# A214B.net
KiCad netlist of a schematic drawn in EAGLE
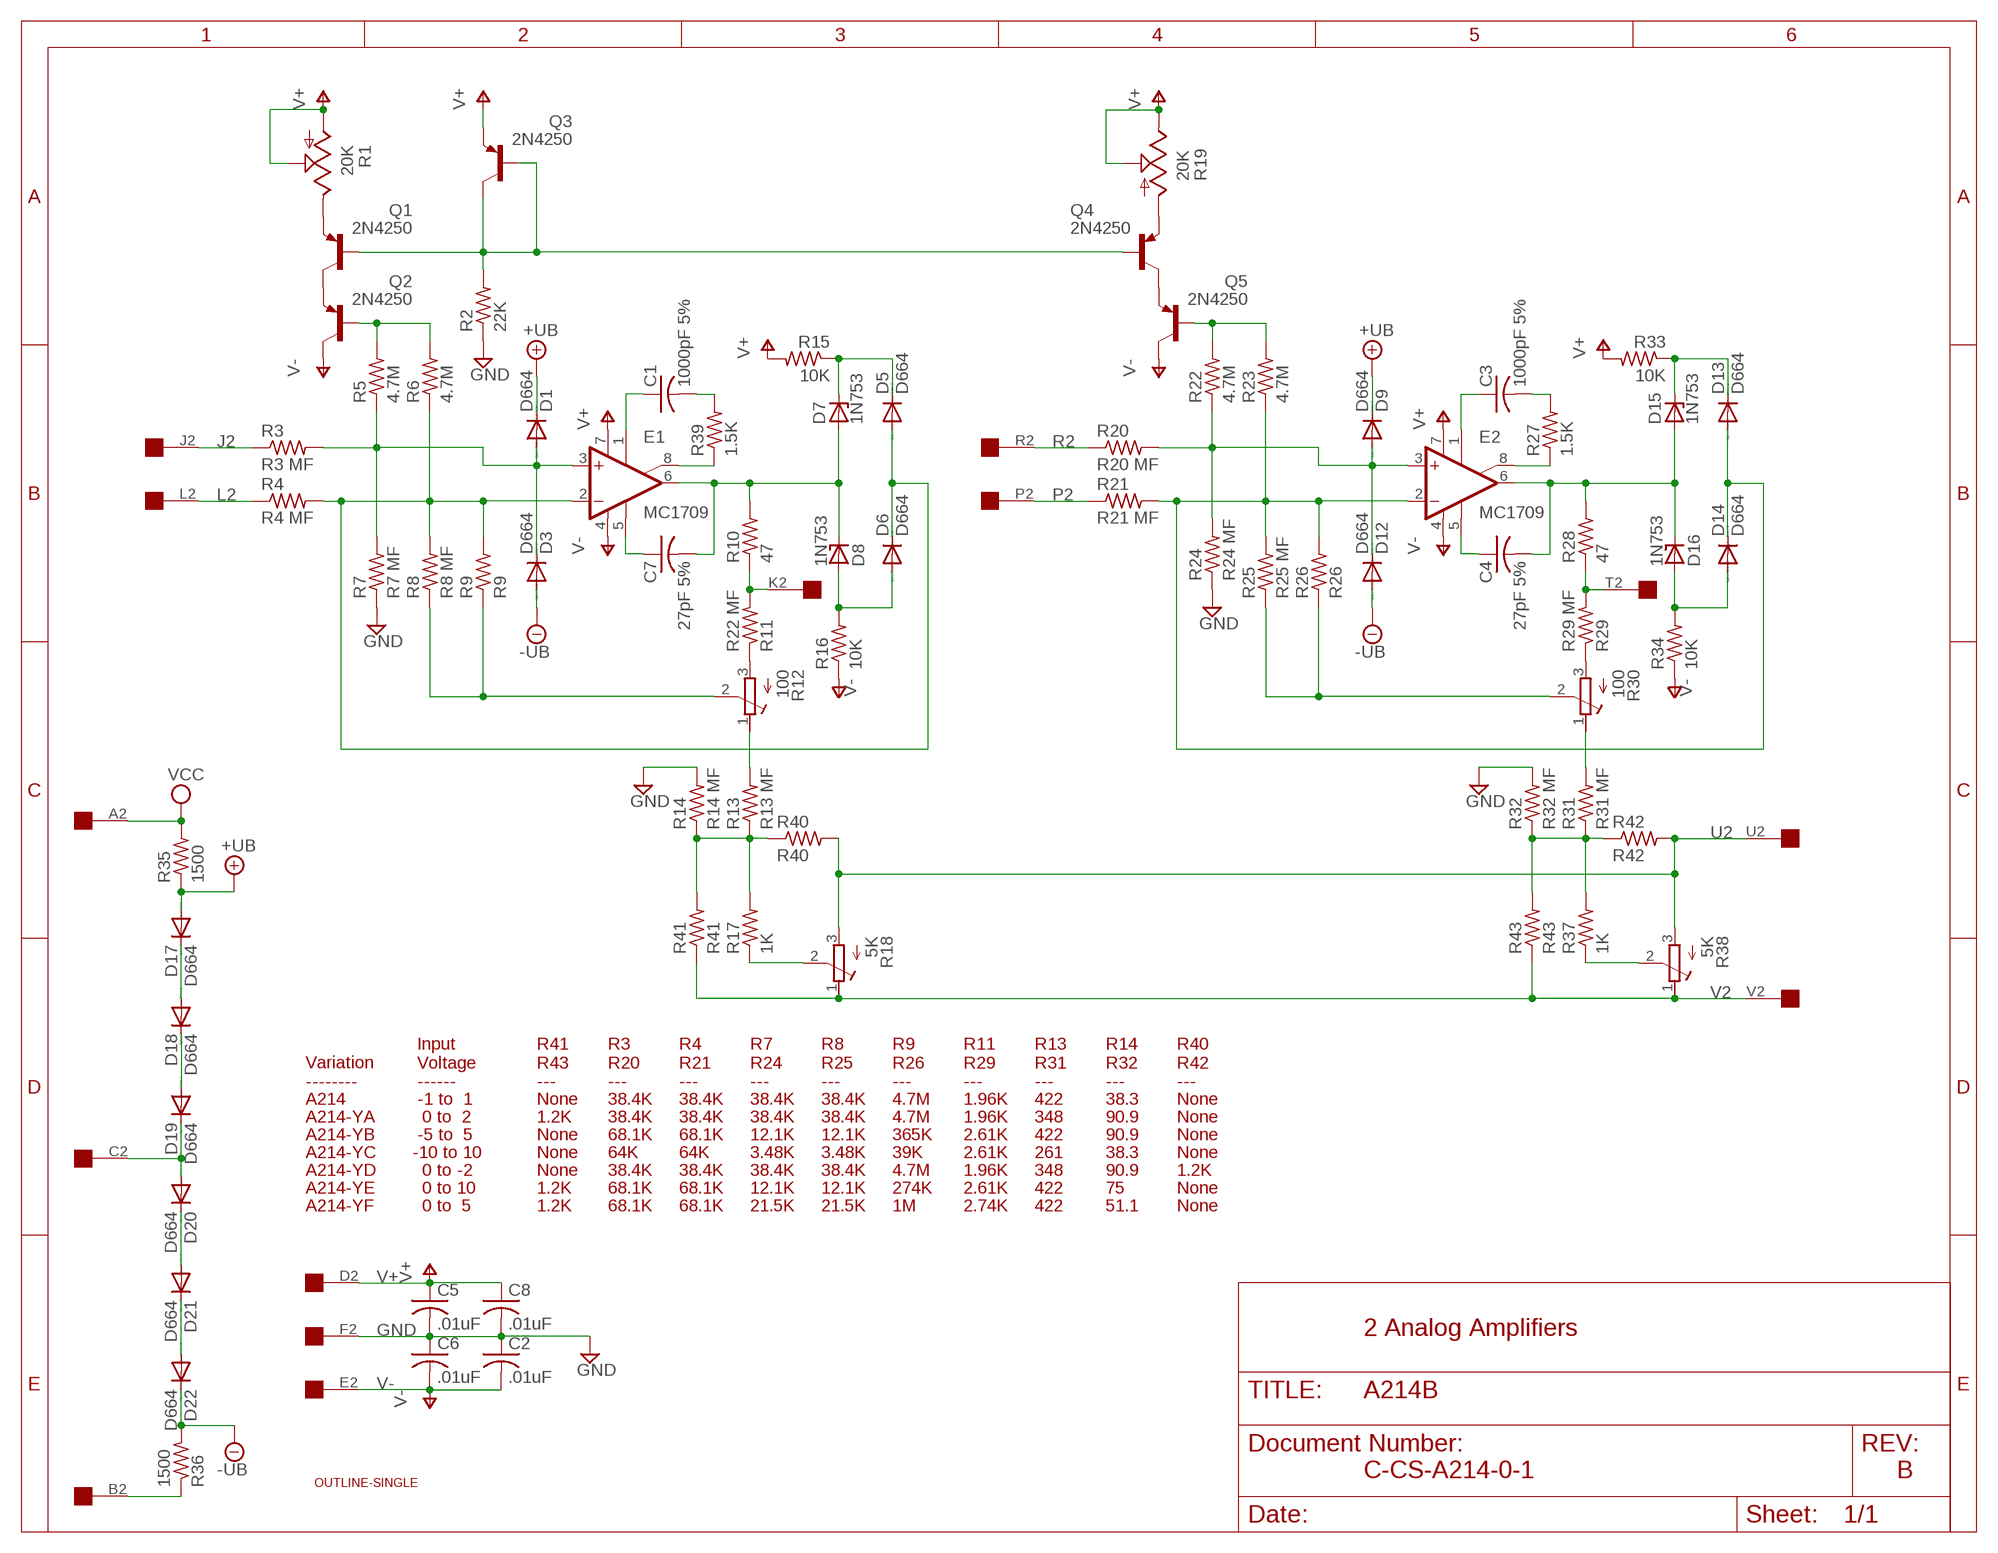
[diagram p0: schematic, sheet 1]

(export (version "E")
  (design (tool "Eeschema 10.0.6"))
  (components
    (comp (ref "C1")
      (value "1000pF 5%")
      (footprint "eagle-import:C050-030X075")
      (libsource (lib "eagle-import") (part "C-US050-030X075"))
    )
    (comp (ref "C2")
      (value ".01uF")
      (footprint "eagle-import:C063-025X075")
      (libsource (lib "eagle-import") (part "C-US"))
    )
    (comp (ref "C3")
      (value "1000pF 5%")
      (footprint "eagle-import:C050-030X075")
      (libsource (lib "eagle-import") (part "C-US050-030X075"))
    )
    (comp (ref "C4")
      (value "27pF 5%")
      (footprint "eagle-import:C063-025X075")
      (libsource (lib "eagle-import") (part "C-US"))
    )
    (comp (ref "C5")
      (value ".01uF")
      (footprint "eagle-import:C063-025X075")
      (libsource (lib "eagle-import") (part "C-US"))
    )
    (comp (ref "C6")
      (value ".01uF")
      (footprint "eagle-import:C063-025X075")
      (libsource (lib "eagle-import") (part "C-US"))
    )
    (comp (ref "C7")
      (value "27pF 5%")
      (footprint "eagle-import:C063-025X075")
      (libsource (lib "eagle-import") (part "C-US"))
    )
    (comp (ref "C8")
      (value ".01uF")
      (footprint "eagle-import:C063-025X075")
      (libsource (lib "eagle-import") (part "C-US"))
    )
    (comp (ref "D1")
      (value "D664")
      (footprint "eagle-import:DO35-10")
      (libsource (lib "eagle-import") (part "DIODE-DO35-10"))
    )
    (comp (ref "D3")
      (value "D664")
      (footprint "eagle-import:DO35-10")
      (libsource (lib "eagle-import") (part "DIODE-DO35-10"))
    )
    (comp (ref "D5")
      (value "D664")
      (footprint "eagle-import:DO35-10")
      (libsource (lib "eagle-import") (part "DIODE-DO35-10"))
    )
    (comp (ref "D6")
      (value "D664")
      (footprint "eagle-import:DO35-10")
      (libsource (lib "eagle-import") (part "DIODE-DO35-10"))
    )
    (comp (ref "D7")
      (value "1N753")
      (footprint "eagle-import:DO41Z10")
      (libsource (lib "eagle-import") (part "ZENER-DIODEDO41Z10"))
    )
    (comp (ref "D8")
      (value "1N753")
      (footprint "eagle-import:DO41Z10")
      (libsource (lib "eagle-import") (part "ZENER-DIODEDO41Z10"))
    )
    (comp (ref "D9")
      (value "D664")
      (footprint "eagle-import:DO35-10")
      (libsource (lib "eagle-import") (part "DIODE-DO35-10"))
    )
    (comp (ref "D12")
      (value "D664")
      (footprint "eagle-import:DO35-10")
      (libsource (lib "eagle-import") (part "DIODE-DO35-10"))
    )
    (comp (ref "D13")
      (value "D664")
      (footprint "eagle-import:DO35-10")
      (libsource (lib "eagle-import") (part "DIODE-DO35-10"))
    )
    (comp (ref "D14")
      (value "D664")
      (footprint "eagle-import:DO35-10")
      (libsource (lib "eagle-import") (part "DIODE-DO35-10"))
    )
    (comp (ref "D15")
      (value "1N753")
      (footprint "eagle-import:DO41Z10")
      (libsource (lib "eagle-import") (part "ZENER-DIODEDO41Z10"))
    )
    (comp (ref "D16")
      (value "1N753")
      (footprint "eagle-import:DO41Z10")
      (libsource (lib "eagle-import") (part "ZENER-DIODEDO41Z10"))
    )
    (comp (ref "D17")
      (value "D664")
      (footprint "eagle-import:DO35-10")
      (libsource (lib "eagle-import") (part "DIODE-DO35-10"))
    )
    (comp (ref "D18")
      (value "D664")
      (footprint "eagle-import:DO35-10")
      (libsource (lib "eagle-import") (part "DIODE-DO35-10"))
    )
    (comp (ref "D19")
      (value "D664")
      (footprint "eagle-import:DO35-10")
      (libsource (lib "eagle-import") (part "DIODE-DO35-10"))
    )
    (comp (ref "D20")
      (value "D664")
      (footprint "eagle-import:DO35-10")
      (libsource (lib "eagle-import") (part "DIODE-DO35-10"))
    )
    (comp (ref "D21")
      (value "D664")
      (footprint "eagle-import:DO35-10")
      (libsource (lib "eagle-import") (part "DIODE-DO35-10"))
    )
    (comp (ref "D22")
      (value "D664")
      (footprint "eagle-import:DO35-10")
      (libsource (lib "eagle-import") (part "DIODE-DO35-10"))
    )
    (comp (ref "E1")
      (value "MC1709")
      (footprint "eagle-import:H08C")
      (libsource (lib "eagle-import") (part "MC1709"))
    )
    (comp (ref "E2")
      (value "MC1709")
      (footprint "eagle-import:H08C")
      (libsource (lib "eagle-import") (part "MC1709"))
    )
    (comp (ref "Q1")
      (value "2N4250")
      (footprint "eagle-import:TO5")
      (libsource (lib "eagle-import") (part "-PNP-TO5"))
    )
    (comp (ref "Q2")
      (value "2N4250")
      (footprint "eagle-import:TO5")
      (libsource (lib "eagle-import") (part "-PNP-TO5"))
    )
    (comp (ref "Q3")
      (value "2N4250")
      (footprint "eagle-import:TO5")
      (libsource (lib "eagle-import") (part "-PNP-TO5"))
    )
    (comp (ref "Q4")
      (value "2N4250")
      (footprint "eagle-import:TO5")
      (libsource (lib "eagle-import") (part "-PNP-TO5"))
    )
    (comp (ref "Q5")
      (value "2N4250")
      (footprint "eagle-import:TO5")
      (libsource (lib "eagle-import") (part "-PNP-TO5"))
    )
    (comp (ref "R1")
      (value "20K")
      (footprint "eagle-import:B25P")
      (libsource (lib "eagle-import") (part "TRIM_US-B25P"))
    )
    (comp (ref "R2")
      (value "22K")
      (footprint "eagle-import:0207_10")
      (libsource (lib "eagle-import") (part "R-US_0207/10"))
    )
    (comp (ref "R3")
      (value "R3 MF")
      (footprint "eagle-import:0207_15")
      (libsource (lib "eagle-import") (part "R-US_0207/15"))
    )
    (comp (ref "R4")
      (value "R4 MF")
      (footprint "eagle-import:0207_15")
      (libsource (lib "eagle-import") (part "R-US_0207/15"))
    )
    (comp (ref "R5")
      (value "4.7M")
      (footprint "eagle-import:0207_10")
      (libsource (lib "eagle-import") (part "R-US_0207/10"))
    )
    (comp (ref "R6")
      (value "4.7M")
      (footprint "eagle-import:0207_10")
      (libsource (lib "eagle-import") (part "R-US_0207/10"))
    )
    (comp (ref "R7")
      (value "R7 MF")
      (footprint "eagle-import:0207_15")
      (libsource (lib "eagle-import") (part "R-US_0207/15"))
    )
    (comp (ref "R8")
      (value "R8 MF")
      (footprint "eagle-import:0207_15")
      (libsource (lib "eagle-import") (part "R-US_0207/15"))
    )
    (comp (ref "R9")
      (value "R9")
      (footprint "eagle-import:0207_10")
      (libsource (lib "eagle-import") (part "R-US_0207/10"))
    )
    (comp (ref "R10")
      (value "47")
      (footprint "eagle-import:0207_10")
      (libsource (lib "eagle-import") (part "R-US_0207/10"))
    )
    (comp (ref "R11")
      (value "R22 MF")
      (footprint "eagle-import:0207_15")
      (libsource (lib "eagle-import") (part "R-US_0207/15"))
    )
    (comp (ref "R12")
      (value "100")
      (footprint "eagle-import:3006Y")
      (libsource (lib "eagle-import") (part "275P"))
    )
    (comp (ref "R13")
      (value "R13 MF")
      (footprint "eagle-import:0207_15")
      (libsource (lib "eagle-import") (part "R-US_0207/15"))
    )
    (comp (ref "R14")
      (value "R14 MF")
      (footprint "eagle-import:0207_15")
      (libsource (lib "eagle-import") (part "R-US_0207/15"))
    )
    (comp (ref "R15")
      (value "10K")
      (footprint "eagle-import:0207_10")
      (libsource (lib "eagle-import") (part "R-US_0207/10"))
    )
    (comp (ref "R16")
      (value "10K")
      (footprint "eagle-import:0207_10")
      (libsource (lib "eagle-import") (part "R-US_0207/10"))
    )
    (comp (ref "R17")
      (value "1K")
      (footprint "eagle-import:0207_10")
      (libsource (lib "eagle-import") (part "R-US_0207/10"))
    )
    (comp (ref "R18")
      (value "5K")
      (footprint "eagle-import:3006Y")
      (libsource (lib "eagle-import") (part "275P"))
    )
    (comp (ref "R19")
      (value "20K")
      (footprint "eagle-import:B25P")
      (libsource (lib "eagle-import") (part "TRIM_US-B25P"))
    )
    (comp (ref "R20")
      (value "R20 MF")
      (footprint "eagle-import:0207_15")
      (libsource (lib "eagle-import") (part "R-US_0207/15"))
    )
    (comp (ref "R21")
      (value "R21 MF")
      (footprint "eagle-import:0207_15")
      (libsource (lib "eagle-import") (part "R-US_0207/15"))
    )
    (comp (ref "R22")
      (value "4.7M")
      (footprint "eagle-import:0207_10")
      (libsource (lib "eagle-import") (part "R-US_0207/10"))
    )
    (comp (ref "R23")
      (value "4.7M")
      (footprint "eagle-import:0207_10")
      (libsource (lib "eagle-import") (part "R-US_0207/10"))
    )
    (comp (ref "R24")
      (value "R24 MF")
      (footprint "eagle-import:0207_15")
      (libsource (lib "eagle-import") (part "R-US_0207/15"))
    )
    (comp (ref "R25")
      (value "R25 MF")
      (footprint "eagle-import:0207_15")
      (libsource (lib "eagle-import") (part "R-US_0207/15"))
    )
    (comp (ref "R26")
      (value "R26")
      (footprint "eagle-import:0207_10")
      (libsource (lib "eagle-import") (part "R-US_0207/10"))
    )
    (comp (ref "R27")
      (value "1.5K")
      (footprint "eagle-import:0207_10")
      (libsource (lib "eagle-import") (part "R-US_0207/10"))
    )
    (comp (ref "R28")
      (value "47")
      (footprint "eagle-import:0207_10")
      (libsource (lib "eagle-import") (part "R-US_0207/10"))
    )
    (comp (ref "R29")
      (value "R29 MF")
      (footprint "eagle-import:0207_15")
      (libsource (lib "eagle-import") (part "R-US_0207/15"))
    )
    (comp (ref "R30")
      (value "100")
      (footprint "eagle-import:3006Y")
      (libsource (lib "eagle-import") (part "275P"))
    )
    (comp (ref "R31")
      (value "R31 MF")
      (footprint "eagle-import:0207_15")
      (libsource (lib "eagle-import") (part "R-US_0207/15"))
    )
    (comp (ref "R32")
      (value "R32 MF")
      (footprint "eagle-import:0207_15")
      (libsource (lib "eagle-import") (part "R-US_0207/15"))
    )
    (comp (ref "R33")
      (value "10K")
      (footprint "eagle-import:0207_10")
      (libsource (lib "eagle-import") (part "R-US_0207/10"))
    )
    (comp (ref "R34")
      (value "10K")
      (footprint "eagle-import:0207_10")
      (libsource (lib "eagle-import") (part "R-US_0207/10"))
    )
    (comp (ref "R35")
      (value "1500")
      (footprint "eagle-import:0207_10")
      (libsource (lib "eagle-import") (part "R-US_0207/10"))
    )
    (comp (ref "R36")
      (value "1500")
      (footprint "eagle-import:0207_10")
      (libsource (lib "eagle-import") (part "R-US_0207/10"))
    )
    (comp (ref "R37")
      (value "1K")
      (footprint "eagle-import:0207_10")
      (libsource (lib "eagle-import") (part "R-US_0207/10"))
    )
    (comp (ref "R38")
      (value "5K")
      (footprint "eagle-import:3006Y")
      (libsource (lib "eagle-import") (part "275P"))
    )
    (comp (ref "R39")
      (value "1.5K")
      (footprint "eagle-import:0207_10")
      (libsource (lib "eagle-import") (part "R-US_0207/10"))
    )
    (comp (ref "R40")
      (value "R40")
      (footprint "eagle-import:0207_10")
      (libsource (lib "eagle-import") (part "R-US_0207/10"))
    )
    (comp (ref "R41")
      (value "R41")
      (footprint "eagle-import:0207_10")
      (libsource (lib "eagle-import") (part "R-US_0207/10"))
    )
    (comp (ref "R42")
      (value "R42")
      (footprint "eagle-import:0207_10")
      (libsource (lib "eagle-import") (part "R-US_0207/10"))
    )
    (comp (ref "R43")
      (value "R43")
      (footprint "eagle-import:0207_10")
      (libsource (lib "eagle-import") (part "R-US_0207/10"))
    )
    (comp (ref "U$1")
      (value "OUTLINE-SINGLE")
      (footprint "eagle-import:SINGLE")
      (libsource (lib "eagle-import") (part "OUTLINE-SINGLE"))
    )
    (comp (ref "U$2")
      (value "SINGLE")
      (footprint "eagle-import:EDGE-CON2")
      (libsource (lib "eagle-import") (part "SINGLE"))
    )
  )
  (nets
    (net (code "1") (name "+UB") (class "Default")
      (node (ref "D1") (pin "C") (pinfunction "C_C") (pintype "passive"))
      (node (ref "D17") (pin "A") (pinfunction "A_A") (pintype "passive"))
      (node (ref "D9") (pin "C") (pinfunction "C_C") (pintype "passive"))
      (node (ref "R35") (pin "1") (pinfunction "1_1") (pintype "passive"))
    )
    (net (code "2") (name "-UB") (class "Default")
      (node (ref "D12") (pin "A") (pinfunction "A_A") (pintype "passive"))
      (node (ref "D22") (pin "C") (pinfunction "C_C") (pintype "passive"))
      (node (ref "D3") (pin "A") (pinfunction "A_A") (pintype "passive"))
      (node (ref "R36") (pin "2") (pinfunction "2_2") (pintype "passive"))
    )
    (net (code "3") (name "/J2") (class "Default")
      (node (ref "R3") (pin "1") (pinfunction "1_1") (pintype "passive"))
      (node (ref "U$2") (pin "J2") (pinfunction "1_J2") (pintype "bidirectional"))
    )
    (net (code "4") (name "/L2") (class "Default")
      (node (ref "R4") (pin "1") (pinfunction "1_1") (pintype "passive"))
      (node (ref "U$2") (pin "L2") (pinfunction "1_L2") (pintype "bidirectional"))
    )
    (net (code "5") (name "/P2") (class "Default")
      (node (ref "R21") (pin "1") (pinfunction "1_1") (pintype "passive"))
      (node (ref "U$2") (pin "P2") (pinfunction "1_P2") (pintype "bidirectional"))
    )
    (net (code "6") (name "/R2") (class "Default")
      (node (ref "R20") (pin "1") (pinfunction "1_1") (pintype "passive"))
      (node (ref "U$2") (pin "R2") (pinfunction "1_R2") (pintype "bidirectional"))
    )
    (net (code "7") (name "/U2") (class "Default")
      (node (ref "R18") (pin "3") (pinfunction "E_3") (pintype "passive"))
      (node (ref "R38") (pin "3") (pinfunction "E_3") (pintype "passive"))
      (node (ref "R40") (pin "2") (pinfunction "2_2") (pintype "passive"))
      (node (ref "R42") (pin "2") (pinfunction "2_2") (pintype "passive"))
      (node (ref "U$2") (pin "U2") (pinfunction "1_U2") (pintype "bidirectional"))
    )
    (net (code "8") (name "/V2") (class "Default")
      (node (ref "R18") (pin "1") (pinfunction "A_1") (pintype "passive"))
      (node (ref "R38") (pin "1") (pinfunction "A_1") (pintype "passive"))
      (node (ref "R41") (pin "1") (pinfunction "1_1") (pintype "passive"))
      (node (ref "R43") (pin "1") (pinfunction "1_1") (pintype "passive"))
      (node (ref "U$2") (pin "V2") (pinfunction "1_V2") (pintype "bidirectional"))
    )
    (net (code "9") (name "GND") (class "Default")
      (node (ref "C2") (pin "1") (pinfunction "1_1") (pintype "passive"))
      (node (ref "C5") (pin "2") (pinfunction "2_2") (pintype "passive"))
      (node (ref "C6") (pin "1") (pinfunction "1_1") (pintype "passive"))
      (node (ref "C8") (pin "2") (pinfunction "2_2") (pintype "passive"))
      (node (ref "R14") (pin "2") (pinfunction "2_2") (pintype "passive"))
      (node (ref "R2") (pin "1") (pinfunction "1_1") (pintype "passive"))
      (node (ref "R24") (pin "1") (pinfunction "1_1") (pintype "passive"))
      (node (ref "R32") (pin "2") (pinfunction "2_2") (pintype "passive"))
      (node (ref "R7") (pin "1") (pinfunction "1_1") (pintype "passive"))
      (node (ref "U$2") (pin "F2") (pinfunction "1_F2") (pintype "bidirectional"))
    )
    (net (code "10") (name "Net-(C1-Pad2)") (class "Default")
      (node (ref "C1") (pin "2") (pinfunction "2_2") (pintype "passive"))
      (node (ref "R39") (pin "2") (pinfunction "2_2") (pintype "passive"))
    )
    (net (code "11") (name "Net-(C3-Pad2)") (class "Default")
      (node (ref "C3") (pin "2") (pinfunction "2_2") (pintype "passive"))
      (node (ref "R27") (pin "2") (pinfunction "2_2") (pintype "passive"))
    )
    (net (code "12") (name "Net-(D5-PadC)") (class "Default")
      (node (ref "D5") (pin "C") (pinfunction "C_C") (pintype "passive"))
      (node (ref "D7") (pin "C") (pinfunction "C_C") (pintype "passive"))
      (node (ref "R15") (pin "1") (pinfunction "1_1") (pintype "passive"))
    )
    (net (code "13") (name "Net-(D6-PadA)") (class "Default")
      (node (ref "D6") (pin "A") (pinfunction "A_A") (pintype "passive"))
      (node (ref "D8") (pin "A") (pinfunction "A_A") (pintype "passive"))
      (node (ref "R16") (pin "2") (pinfunction "2_2") (pintype "passive"))
    )
    (net (code "14") (name "Net-(D13-PadC)") (class "Default")
      (node (ref "D13") (pin "C") (pinfunction "C_C") (pintype "passive"))
      (node (ref "D15") (pin "C") (pinfunction "C_C") (pintype "passive"))
      (node (ref "R33") (pin "1") (pinfunction "1_1") (pintype "passive"))
    )
    (net (code "15") (name "Net-(D14-PadA)") (class "Default")
      (node (ref "D14") (pin "A") (pinfunction "A_A") (pintype "passive"))
      (node (ref "D16") (pin "A") (pinfunction "A_A") (pintype "passive"))
      (node (ref "R34") (pin "2") (pinfunction "2_2") (pintype "passive"))
    )
    (net (code "16") (name "Net-(D17-PadC)") (class "Default")
      (node (ref "D17") (pin "C") (pinfunction "C_C") (pintype "passive"))
      (node (ref "D18") (pin "A") (pinfunction "A_A") (pintype "passive"))
    )
    (net (code "17") (name "Net-(D18-PadC)") (class "Default")
      (node (ref "D18") (pin "C") (pinfunction "C_C") (pintype "passive"))
      (node (ref "D19") (pin "A") (pinfunction "A_A") (pintype "passive"))
    )
    (net (code "18") (name "Net-(D20-PadC)") (class "Default")
      (node (ref "D20") (pin "C") (pinfunction "C_C") (pintype "passive"))
      (node (ref "D21") (pin "A") (pinfunction "A_A") (pintype "passive"))
    )
    (net (code "19") (name "Net-(D21-PadC)") (class "Default")
      (node (ref "D21") (pin "C") (pinfunction "C_C") (pintype "passive"))
      (node (ref "D22") (pin "A") (pinfunction "A_A") (pintype "passive"))
    )
    (net (code "20") (name "Net-(E1-+IN)") (class "Default")
      (node (ref "D1") (pin "A") (pinfunction "A_A") (pintype "passive"))
      (node (ref "D3") (pin "C") (pinfunction "C_C") (pintype "passive"))
      (node (ref "E1") (pin "3") (pinfunction "+IN_3") (pintype "input"))
      (node (ref "R3") (pin "2") (pinfunction "2_2") (pintype "passive"))
      (node (ref "R5") (pin "1") (pinfunction "1_1") (pintype "passive"))
      (node (ref "R7") (pin "2") (pinfunction "2_2") (pintype "passive"))
    )
    (net (code "21") (name "Net-(E1--IN)") (class "Default")
      (node (ref "D5") (pin "A") (pinfunction "A_A") (pintype "passive"))
      (node (ref "D6") (pin "C") (pinfunction "C_C") (pintype "passive"))
      (node (ref "E1") (pin "2") (pinfunction "-IN_2") (pintype "input"))
      (node (ref "R4") (pin "2") (pinfunction "2_2") (pintype "passive"))
      (node (ref "R6") (pin "1") (pinfunction "1_1") (pintype "passive"))
      (node (ref "R8") (pin "2") (pinfunction "2_2") (pintype "passive"))
      (node (ref "R9") (pin "2") (pinfunction "2_2") (pintype "passive"))
    )
    (net (code "22") (name "Net-(E1-ON1)") (class "Default")
      (node (ref "C1") (pin "1") (pinfunction "1_1") (pintype "passive"))
      (node (ref "E1") (pin "1") (pinfunction "ON1_1") (pintype "passive"))
    )
    (net (code "23") (name "Net-(E1-ON2)") (class "Default")
      (node (ref "E1") (pin "8") (pinfunction "ON2_8") (pintype "passive"))
      (node (ref "R39") (pin "1") (pinfunction "1_1") (pintype "passive"))
    )
    (net (code "24") (name "Net-(E1-OPT)") (class "Default")
      (node (ref "C7") (pin "1") (pinfunction "1_1") (pintype "passive"))
      (node (ref "E1") (pin "5") (pinfunction "OPT_5") (pintype "passive"))
    )
    (net (code "25") (name "Net-(E1-OUT)") (class "Default")
      (node (ref "C7") (pin "2") (pinfunction "2_2") (pintype "passive"))
      (node (ref "D7") (pin "A") (pinfunction "A_A") (pintype "passive"))
      (node (ref "D8") (pin "C") (pinfunction "C_C") (pintype "passive"))
      (node (ref "E1") (pin "6") (pinfunction "OUT_6") (pintype "output"))
      (node (ref "R10") (pin "2") (pinfunction "2_2") (pintype "passive"))
    )
    (net (code "26") (name "Net-(E2-+IN)") (class "Default")
      (node (ref "D12") (pin "C") (pinfunction "C_C") (pintype "passive"))
      (node (ref "D9") (pin "A") (pinfunction "A_A") (pintype "passive"))
      (node (ref "E2") (pin "3") (pinfunction "+IN_3") (pintype "input"))
      (node (ref "R20") (pin "2") (pinfunction "2_2") (pintype "passive"))
      (node (ref "R22") (pin "1") (pinfunction "1_1") (pintype "passive"))
      (node (ref "R24") (pin "2") (pinfunction "2_2") (pintype "passive"))
    )
    (net (code "27") (name "Net-(E2--IN)") (class "Default")
      (node (ref "D13") (pin "A") (pinfunction "A_A") (pintype "passive"))
      (node (ref "D14") (pin "C") (pinfunction "C_C") (pintype "passive"))
      (node (ref "E2") (pin "2") (pinfunction "-IN_2") (pintype "input"))
      (node (ref "R21") (pin "2") (pinfunction "2_2") (pintype "passive"))
      (node (ref "R23") (pin "1") (pinfunction "1_1") (pintype "passive"))
      (node (ref "R25") (pin "2") (pinfunction "2_2") (pintype "passive"))
      (node (ref "R26") (pin "2") (pinfunction "2_2") (pintype "passive"))
    )
    (net (code "28") (name "Net-(E2-ON1)") (class "Default")
      (node (ref "C3") (pin "1") (pinfunction "1_1") (pintype "passive"))
      (node (ref "E2") (pin "1") (pinfunction "ON1_1") (pintype "passive"))
    )
    (net (code "29") (name "Net-(E2-ON2)") (class "Default")
      (node (ref "E2") (pin "8") (pinfunction "ON2_8") (pintype "passive"))
      (node (ref "R27") (pin "1") (pinfunction "1_1") (pintype "passive"))
    )
    (net (code "30") (name "Net-(E2-OPT)") (class "Default")
      (node (ref "C4") (pin "1") (pinfunction "1_1") (pintype "passive"))
      (node (ref "E2") (pin "5") (pinfunction "OPT_5") (pintype "passive"))
    )
    (net (code "31") (name "Net-(E2-OUT)") (class "Default")
      (node (ref "C4") (pin "2") (pinfunction "2_2") (pintype "passive"))
      (node (ref "D15") (pin "A") (pinfunction "A_A") (pintype "passive"))
      (node (ref "D16") (pin "C") (pinfunction "C_C") (pintype "passive"))
      (node (ref "E2") (pin "6") (pinfunction "OUT_6") (pintype "output"))
      (node (ref "R28") (pin "2") (pinfunction "2_2") (pintype "passive"))
    )
    (net (code "32") (name "Net-(Q1-B)") (class "Default")
      (node (ref "Q1") (pin "2") (pinfunction "B_2") (pintype "passive"))
      (node (ref "Q3") (pin "2") (pinfunction "B_2") (pintype "passive"))
      (node (ref "Q3") (pin "3") (pinfunction "C_3") (pintype "passive"))
      (node (ref "Q4") (pin "2") (pinfunction "B_2") (pintype "passive"))
      (node (ref "R2") (pin "2") (pinfunction "2_2") (pintype "passive"))
    )
    (net (code "33") (name "Net-(Q1-C)") (class "Default")
      (node (ref "Q1") (pin "3") (pinfunction "C_3") (pintype "passive"))
      (node (ref "Q2") (pin "1") (pinfunction "E_1") (pintype "passive"))
    )
    (net (code "34") (name "Net-(Q1-E)") (class "Default")
      (node (ref "Q1") (pin "1") (pinfunction "E_1") (pintype "passive"))
      (node (ref "R1") (pin "E") (pinfunction "E_E") (pintype "passive"))
    )
    (net (code "35") (name "Net-(Q2-B)") (class "Default")
      (node (ref "Q2") (pin "2") (pinfunction "B_2") (pintype "passive"))
      (node (ref "R5") (pin "2") (pinfunction "2_2") (pintype "passive"))
      (node (ref "R6") (pin "2") (pinfunction "2_2") (pintype "passive"))
    )
    (net (code "36") (name "Net-(Q4-C)") (class "Default")
      (node (ref "Q4") (pin "3") (pinfunction "C_3") (pintype "passive"))
      (node (ref "Q5") (pin "1") (pinfunction "E_1") (pintype "passive"))
    )
    (net (code "37") (name "Net-(Q4-E)") (class "Default")
      (node (ref "Q4") (pin "1") (pinfunction "E_1") (pintype "passive"))
      (node (ref "R19") (pin "A") (pinfunction "A_A") (pintype "passive"))
    )
    (net (code "38") (name "Net-(Q5-B)") (class "Default")
      (node (ref "Q5") (pin "2") (pinfunction "B_2") (pintype "passive"))
      (node (ref "R22") (pin "2") (pinfunction "2_2") (pintype "passive"))
      (node (ref "R23") (pin "2") (pinfunction "2_2") (pintype "passive"))
    )
    (net (code "39") (name "Net-(R12-A)") (class "Default")
      (node (ref "R12") (pin "1") (pinfunction "A_1") (pintype "passive"))
      (node (ref "R13") (pin "2") (pinfunction "2_2") (pintype "passive"))
    )
    (net (code "40") (name "Net-(R12-E)") (class "Default")
      (node (ref "R11") (pin "1") (pinfunction "1_1") (pintype "passive"))
      (node (ref "R12") (pin "3") (pinfunction "E_3") (pintype "passive"))
    )
    (net (code "41") (name "Net-(R12-S)") (class "Default")
      (node (ref "R12") (pin "2") (pinfunction "S_2") (pintype "passive"))
      (node (ref "R8") (pin "1") (pinfunction "1_1") (pintype "passive"))
      (node (ref "R9") (pin "1") (pinfunction "1_1") (pintype "passive"))
    )
    (net (code "42") (name "Net-(R13-Pad1)") (class "Default")
      (node (ref "R13") (pin "1") (pinfunction "1_1") (pintype "passive"))
      (node (ref "R14") (pin "1") (pinfunction "1_1") (pintype "passive"))
      (node (ref "R17") (pin "2") (pinfunction "2_2") (pintype "passive"))
      (node (ref "R40") (pin "1") (pinfunction "1_1") (pintype "passive"))
      (node (ref "R41") (pin "2") (pinfunction "2_2") (pintype "passive"))
    )
    (net (code "43") (name "Net-(R18-S)") (class "Default")
      (node (ref "R17") (pin "1") (pinfunction "1_1") (pintype "passive"))
      (node (ref "R18") (pin "2") (pinfunction "S_2") (pintype "passive"))
    )
    (net (code "44") (name "Net-(R30-A)") (class "Default")
      (node (ref "R30") (pin "1") (pinfunction "A_1") (pintype "passive"))
      (node (ref "R31") (pin "2") (pinfunction "2_2") (pintype "passive"))
    )
    (net (code "45") (name "Net-(R30-E)") (class "Default")
      (node (ref "R29") (pin "1") (pinfunction "1_1") (pintype "passive"))
      (node (ref "R30") (pin "3") (pinfunction "E_3") (pintype "passive"))
    )
    (net (code "46") (name "Net-(R30-S)") (class "Default")
      (node (ref "R25") (pin "1") (pinfunction "1_1") (pintype "passive"))
      (node (ref "R26") (pin "1") (pinfunction "1_1") (pintype "passive"))
      (node (ref "R30") (pin "2") (pinfunction "S_2") (pintype "passive"))
    )
    (net (code "47") (name "Net-(R31-Pad1)") (class "Default")
      (node (ref "R31") (pin "1") (pinfunction "1_1") (pintype "passive"))
      (node (ref "R32") (pin "1") (pinfunction "1_1") (pintype "passive"))
      (node (ref "R37") (pin "2") (pinfunction "2_2") (pintype "passive"))
      (node (ref "R42") (pin "1") (pinfunction "1_1") (pintype "passive"))
      (node (ref "R43") (pin "2") (pinfunction "2_2") (pintype "passive"))
    )
    (net (code "48") (name "Net-(R38-S)") (class "Default")
      (node (ref "R37") (pin "1") (pinfunction "1_1") (pintype "passive"))
      (node (ref "R38") (pin "2") (pinfunction "S_2") (pintype "passive"))
    )
    (net (code "49") (name "Net-(U$2AF-1)") (class "Default")
      (node (ref "R28") (pin "1") (pinfunction "1_1") (pintype "passive"))
      (node (ref "R29") (pin "2") (pinfunction "2_2") (pintype "passive"))
      (node (ref "U$2") (pin "T2") (pinfunction "1_T2") (pintype "bidirectional"))
    )
    (net (code "50") (name "Net-(U$2D-1)") (class "Default")
      (node (ref "R36") (pin "1") (pinfunction "1_1") (pintype "passive"))
      (node (ref "U$2") (pin "B2") (pinfunction "1_B2") (pintype "bidirectional"))
    )
    (net (code "51") (name "Net-(U$2F-1)") (class "Default")
      (node (ref "D19") (pin "C") (pinfunction "C_C") (pintype "passive"))
      (node (ref "D20") (pin "A") (pinfunction "A_A") (pintype "passive"))
      (node (ref "U$2") (pin "C2") (pinfunction "1_C2") (pintype "bidirectional"))
    )
    (net (code "52") (name "Net-(U$2R-1)") (class "Default")
      (node (ref "R10") (pin "1") (pinfunction "1_1") (pintype "passive"))
      (node (ref "R11") (pin "2") (pinfunction "2_2") (pintype "passive"))
      (node (ref "U$2") (pin "K2") (pinfunction "1_K2") (pintype "bidirectional"))
    )
    (net (code "53") (name "V+") (class "Default")
      (node (ref "C5") (pin "1") (pinfunction "1_1") (pintype "passive"))
      (node (ref "C8") (pin "1") (pinfunction "1_1") (pintype "passive"))
      (node (ref "E1") (pin "7") (pinfunction "V+_7") (pintype "power_in"))
      (node (ref "E2") (pin "7") (pinfunction "V+_7") (pintype "power_in"))
      (node (ref "Q3") (pin "1") (pinfunction "E_1") (pintype "passive"))
      (node (ref "R1") (pin "A") (pinfunction "A_A") (pintype "passive"))
      (node (ref "R1") (pin "S") (pinfunction "S_S") (pintype "passive"))
      (node (ref "R15") (pin "2") (pinfunction "2_2") (pintype "passive"))
      (node (ref "R19") (pin "E") (pinfunction "E_E") (pintype "passive"))
      (node (ref "R19") (pin "S") (pinfunction "S_S") (pintype "passive"))
      (node (ref "R33") (pin "2") (pinfunction "2_2") (pintype "passive"))
      (node (ref "U$2") (pin "D2") (pinfunction "1_D2") (pintype "bidirectional"))
    )
    (net (code "54") (name "V-") (class "Default")
      (node (ref "C2") (pin "2") (pinfunction "2_2") (pintype "passive"))
      (node (ref "C6") (pin "2") (pinfunction "2_2") (pintype "passive"))
      (node (ref "E1") (pin "4") (pinfunction "V-_4") (pintype "power_in"))
      (node (ref "E2") (pin "4") (pinfunction "V-_4") (pintype "power_in"))
      (node (ref "Q2") (pin "3") (pinfunction "C_3") (pintype "passive"))
      (node (ref "Q5") (pin "3") (pinfunction "C_3") (pintype "passive"))
      (node (ref "R16") (pin "1") (pinfunction "1_1") (pintype "passive"))
      (node (ref "R34") (pin "1") (pinfunction "1_1") (pintype "passive"))
      (node (ref "U$2") (pin "E2") (pinfunction "1_E2") (pintype "bidirectional"))
    )
    (net (code "55") (name "VCC") (class "Default")
      (node (ref "R35") (pin "2") (pinfunction "2_2") (pintype "passive"))
      (node (ref "U$2") (pin "A2") (pinfunction "1_A2") (pintype "bidirectional"))
    )
  )
)
